# Sheet1.net
KiCad netlist of a schematic drawn in Altium Designer
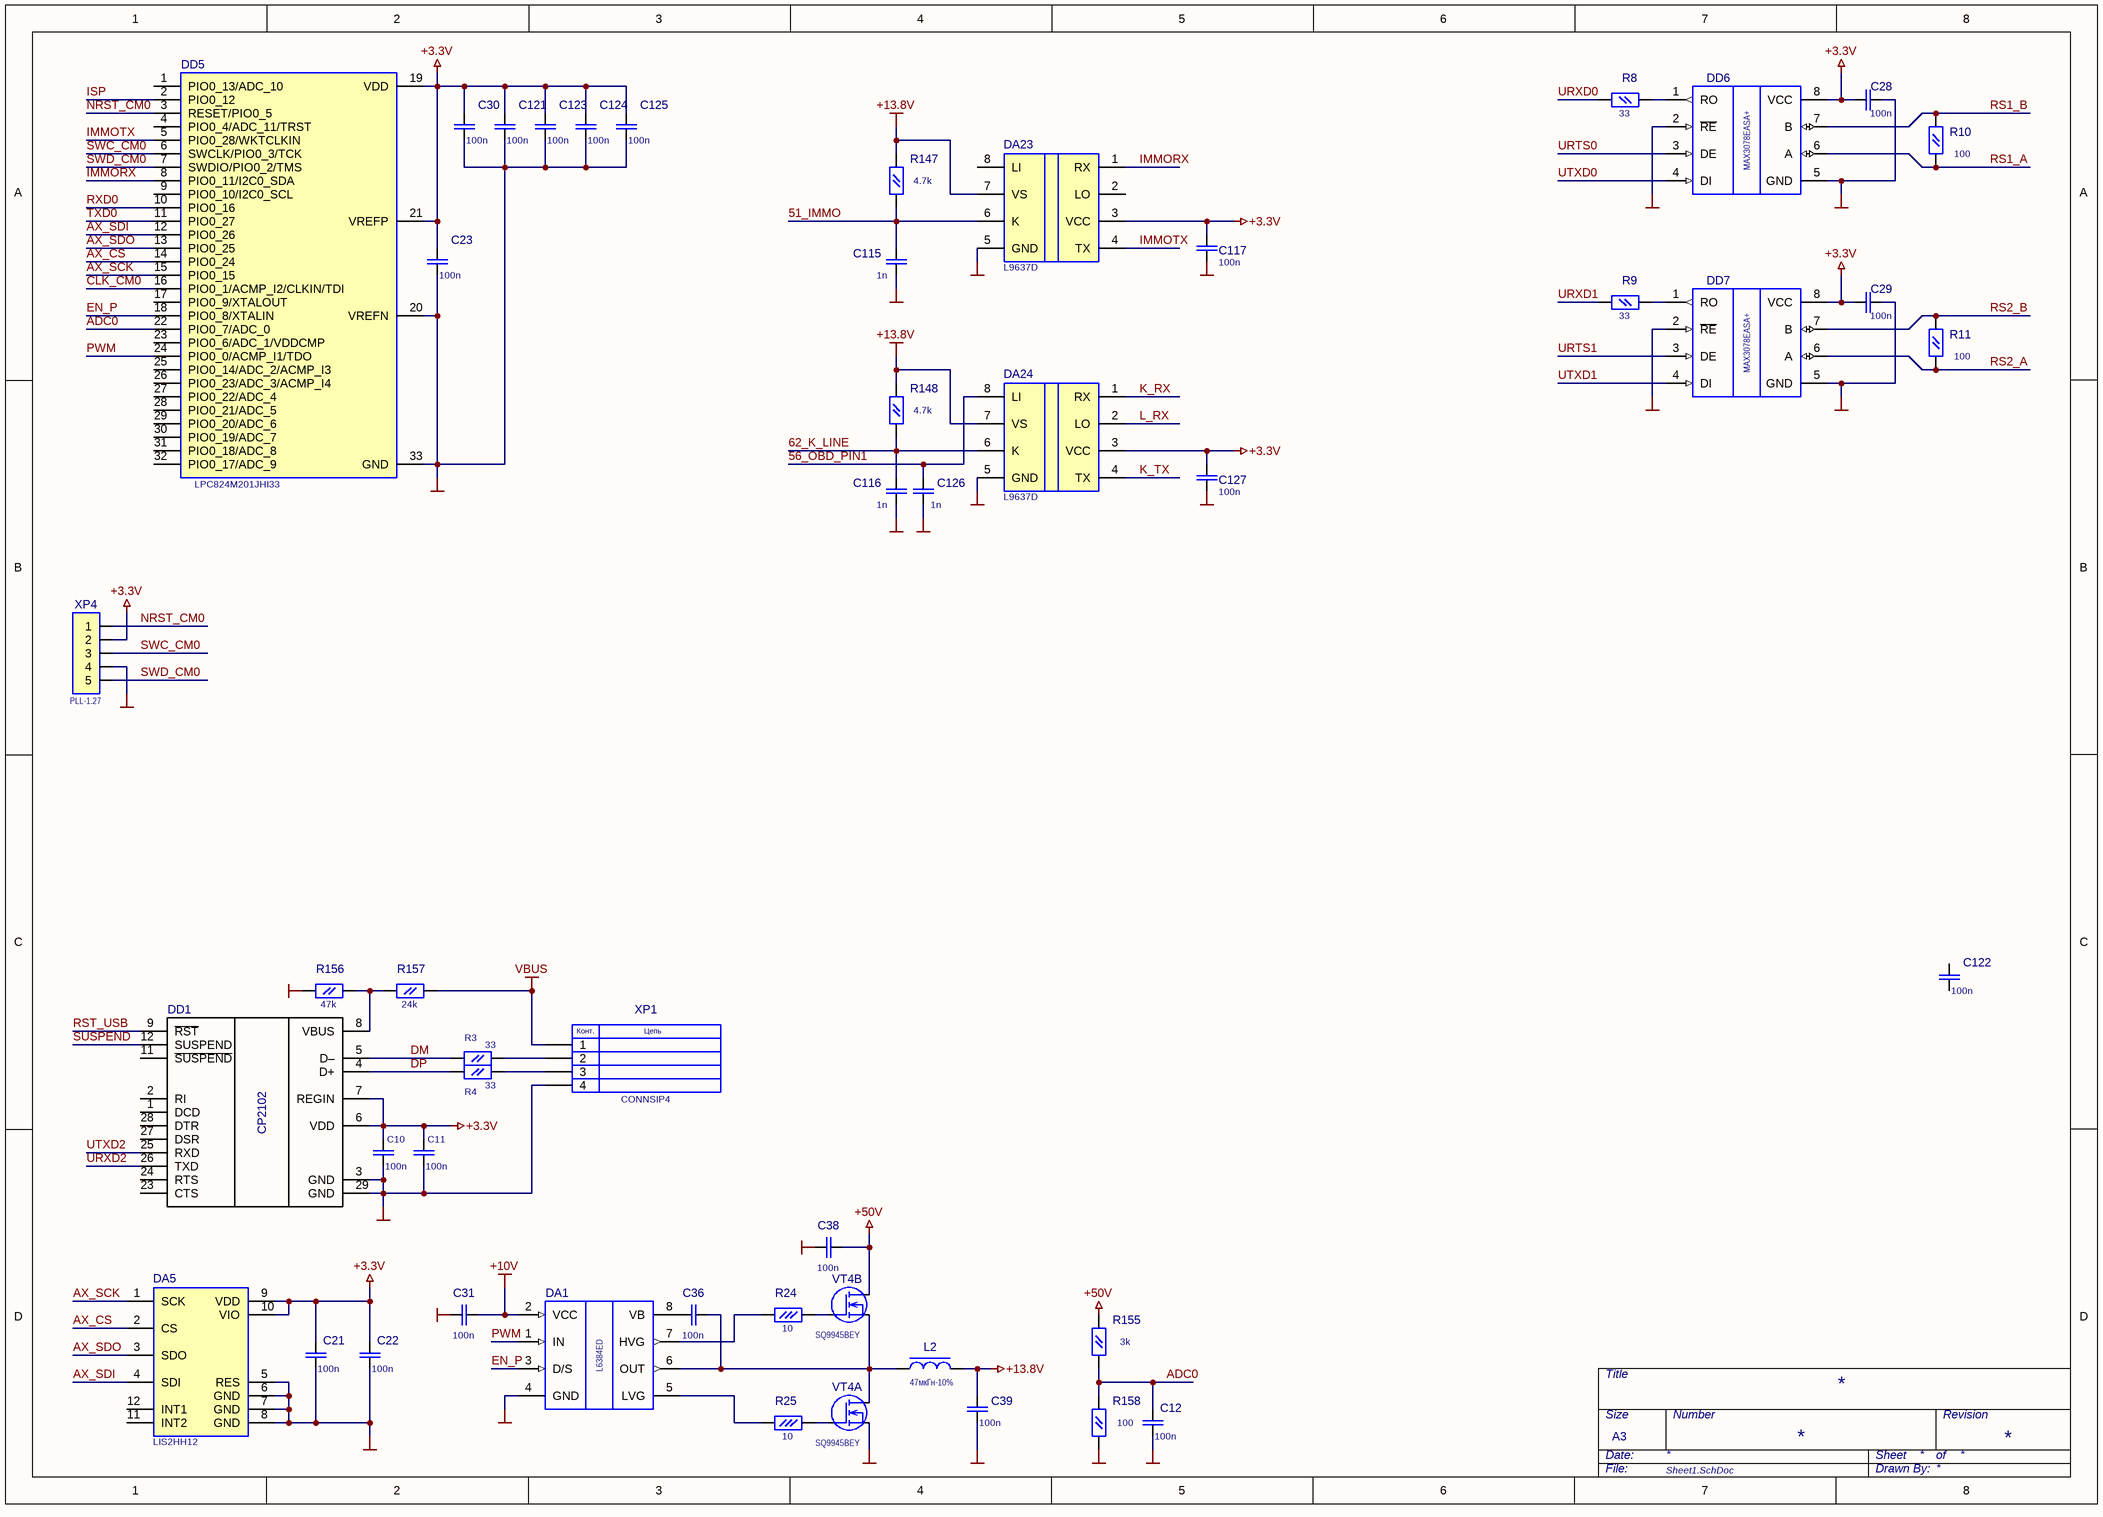
[diagram p0: Sheet1.SchDoc]

(export (version "E")
  (design (tool "Eeschema 10.0.6"))
  (components
    (comp (ref "C10")
      (value "100n")
      (footprint "C0603L")
      (description "C0603")
      (fields (field (name "Comment") "CSMD"))
      (libsource (lib "L1") (part "CSMD"))
    )
    (comp (ref "C11")
      (value "100n")
      (footprint "C0603L")
      (description "C0603")
      (fields (field (name "Comment") "CSMD"))
      (libsource (lib "L1") (part "CSMD"))
    )
    (comp (ref "C12")
      (value "100n")
      (footprint "C0805L")
      (description "C0603")
      (fields (field (name "Comment") "0.1мкФ-25В-X8R-10%"))
      (libsource (lib "L1") (part "CSMD"))
    )
    (comp (ref "C21")
      (value "100n")
      (footprint "C0805L")
      (description "C0603")
      (fields (field (name "Comment") "0.1мкФ-25В-X8R-10%"))
      (libsource (lib "L1") (part "CSMD"))
    )
    (comp (ref "C22")
      (value "100n")
      (footprint "C0805L")
      (description "C0603")
      (fields (field (name "Comment") "0.1мкФ-25В-X8R-10%"))
      (libsource (lib "L1") (part "CSMD"))
    )
    (comp (ref "C23")
      (value "100n")
      (footprint "C0603L")
      (description "C0603")
      (fields (field (name "Comment") "0.1мкФ-25В-X8R-10%"))
      (libsource (lib "L1") (part "CSMD"))
    )
    (comp (ref "C28")
      (value "100n")
      (footprint "C0805")
      (description "C0603")
      (fields (field (name "Comment") "0.1мкФ-50В-X8R-10%"))
      (libsource (lib "L1") (part "CSMD"))
    )
    (comp (ref "C29")
      (value "100n")
      (footprint "C0805")
      (description "C0603")
      (fields (field (name "Comment") "0.1мкФ-50В-X8R-10%"))
      (libsource (lib "L1") (part "CSMD"))
    )
    (comp (ref "C30")
      (value "100n")
      (footprint "C0603L")
      (description "C0603")
      (fields (field (name "Comment") "0.1мкФ-25В-X8R-10%"))
      (libsource (lib "L1") (part "CSMD"))
    )
    (comp (ref "C31")
      (value "100n")
      (footprint "C0805L")
      (description "C0603")
      (fields (field (name "Comment") "CSMD"))
      (libsource (lib "L1") (part "CSMD"))
    )
    (comp (ref "C36")
      (value "100n")
      (footprint "C0805L")
      (description "C0603")
      (fields (field (name "Comment") "CSMD"))
      (libsource (lib "L1") (part "CSMD"))
    )
    (comp (ref "C38")
      (value "100n")
      (footprint "C0805L")
      (description "C0603")
      (fields (field (name "Comment") "CSMD"))
      (libsource (lib "L1") (part "CSMD"))
    )
    (comp (ref "C39")
      (value "100n")
      (footprint "C0805L")
      (description "C0603")
      (fields (field (name "Comment") "0.1мкФ-25В-X8R-10%"))
      (libsource (lib "L1") (part "CSMD"))
    )
    (comp (ref "C115")
      (value "1n")
      (footprint "C0805L")
      (description "C0603")
      (fields (field (name "Comment") "CSMD"))
      (libsource (lib "L1") (part "CSMD"))
    )
    (comp (ref "C116")
      (value "1n")
      (footprint "C0805L")
      (description "C0603")
      (fields (field (name "Comment") "CSMD"))
      (libsource (lib "L1") (part "CSMD"))
    )
    (comp (ref "C117")
      (value "100n")
      (footprint "C0805L")
      (description "C0603")
      (fields (field (name "Comment") "1мкФ-25В-X7R-10%"))
      (libsource (lib "L1") (part "CSMD"))
    )
    (comp (ref "C121")
      (value "100n")
      (footprint "C0603L")
      (description "C0603")
      (fields (field (name "Comment") "0.1мкФ-25В-X8R-10%"))
      (libsource (lib "L1") (part "CSMD"))
    )
    (comp (ref "C122")
      (value "100n")
      (footprint "C0805L")
      (description "C0603")
      (fields (field (name "Comment") "0.1мкФ-50В-X8R-10%"))
      (libsource (lib "L1") (part "CSMD"))
    )
    (comp (ref "C123")
      (value "100n")
      (footprint "C0603L")
      (description "C0603")
      (fields (field (name "Comment") "0.1мкФ-25В-X8R-10%"))
      (libsource (lib "L1") (part "CSMD"))
    )
    (comp (ref "C124")
      (value "100n")
      (footprint "C0603L")
      (description "C0603")
      (fields (field (name "Comment") "0.1мкФ-25В-X8R-10%"))
      (libsource (lib "L1") (part "CSMD"))
    )
    (comp (ref "C125")
      (value "100n")
      (footprint "C0603L")
      (description "C0603")
      (fields (field (name "Comment") "0.1мкФ-25В-X8R-10%"))
      (libsource (lib "L1") (part "CSMD"))
    )
    (comp (ref "C126")
      (value "1n")
      (footprint "C0805L")
      (description "C0603")
      (fields (field (name "Comment") "CSMD"))
      (libsource (lib "L1") (part "CSMD"))
    )
    (comp (ref "C127")
      (value "100n")
      (footprint "C0805L")
      (description "C0603")
      (fields (field (name "Comment") "1мкФ-25В-X7R-10%"))
      (libsource (lib "L1") (part "CSMD"))
    )
    (comp (ref "DA1") (value "L6384ED") (footprint "SOIC8 JEDEC") (libsource (lib "ECULIB") (part "L6384ED")))
    (comp (ref "DA5")
      (value "LIS2HH12")
      (footprint "LGA-12")
      (description "ultra-low-power high-performance 3-axis \"pico\" accelerometer")
      (libsource (lib "L1") (part "LIS2HH12"))
    )
    (comp (ref "DA23")
      (value "L9637D")
      (footprint "SOIC8 JEDEC")
      (description "Monolithic bus driver with ISO 9141 interface")
      (libsource (lib "L1") (part "L9637"))
    )
    (comp (ref "DA24")
      (value "L9637D")
      (footprint "SOIC8 JEDEC")
      (description "Monolithic bus driver with ISO 9141 interface")
      (libsource (lib "L1") (part "L9637"))
    )
    (comp (ref "DD1") (value "CP2102") (footprint "QFN-28") (libsource (lib "L1") (part "CP2102")))
    (comp (ref "DD5")
      (value "LPC824M201JHI33")
      (footprint "HVQFN33")
      (libsource (lib "L1") (part "LPC824M201JHI33"))
    )
    (comp (ref "DD6")
      (value "MAX3078EASA+")
      (footprint "SOIC8 JEDEC")
      (description "MAX3078EASA+ или ISL3179EFBZ или ADM3078EYRZ")
      (libsource (lib "RL1") (part "MAX3088ESA"))
    )
    (comp (ref "DD7")
      (value "MAX3078EASA+")
      (footprint "SOIC8 JEDEC")
      (description "MAX3078EASA+ или ISL3179EFBZ или ADM3078EYRZ")
      (libsource (lib "RL1") (part "MAX3088ESA"))
    )
    (comp (ref "L2") (value "47мкГн-10%") (footprint "L_SDR0604") (libsource (lib "*") (part "DROSSEL3")))
    (comp (ref "R3")
      (value "33")
      (footprint "R0603L")
      (description "R0805")
      (fields (field (name "Comment") "RSMD"))
      (libsource (lib "L1") (part "RSMD"))
    )
    (comp (ref "R4")
      (value "33")
      (footprint "R0603L")
      (description "R0805")
      (fields (field (name "Comment") "RSMD"))
      (libsource (lib "L1") (part "RSMD"))
    )
    (comp (ref "R8")
      (value "33")
      (footprint "R0603L")
      (description "R0805")
      (fields (field (name "Comment") "33-5%"))
      (libsource (lib "L1") (part "RSMD"))
    )
    (comp (ref "R9")
      (value "33")
      (footprint "R0603L")
      (description "R0805")
      (fields (field (name "Comment") "33-5%"))
      (libsource (lib "L1") (part "RSMD"))
    )
    (comp (ref "R10")
      (value "100")
      (footprint "R0805L")
      (description "R0805")
      (fields (field (name "Comment") "100-5%"))
      (libsource (lib "L1") (part "RSMD"))
    )
    (comp (ref "R11")
      (value "100")
      (footprint "R0805L")
      (description "R0805")
      (fields (field (name "Comment") "100-5%"))
      (libsource (lib "L1") (part "RSMD"))
    )
    (comp (ref "R24")
      (value "10")
      (footprint "R0603L")
      (description "R0805")
      (fields (field (name "Comment") "100-5%"))
      (libsource (lib "") (part "RSMD_1"))
    )
    (comp (ref "R25")
      (value "10")
      (footprint "R0603L")
      (description "R0805")
      (fields (field (name "Comment") "100-5%"))
      (libsource (lib "") (part "RSMD_1"))
    )
    (comp (ref "R147")
      (value "4.7k")
      (footprint "R0805L")
      (description "R0805")
      (fields (field (name "Comment") "RSMD"))
      (libsource (lib "L1") (part "RSMD"))
    )
    (comp (ref "R148")
      (value "4.7k")
      (footprint "R0805L")
      (description "R0805")
      (fields (field (name "Comment") "RSMD"))
      (libsource (lib "L1") (part "RSMD"))
    )
    (comp (ref "R155")
      (value "3k")
      (footprint "R0805L")
      (description "R0805")
      (fields (field (name "Comment") "RSMD"))
      (libsource (lib "L1") (part "RSMD"))
    )
    (comp (ref "R156")
      (value "47k")
      (footprint "R0805L")
      (description "R0805")
      (fields (field (name "Comment") "RSMD"))
      (libsource (lib "L1") (part "RSMD"))
    )
    (comp (ref "R157")
      (value "24k")
      (footprint "R0805L")
      (description "R0805")
      (fields (field (name "Comment") "RSMD"))
      (libsource (lib "L1") (part "RSMD"))
    )
    (comp (ref "R158")
      (value "100")
      (footprint "R0805L")
      (description "R0805")
      (fields (field (name "Comment") "RSMD"))
      (libsource (lib "L1") (part "RSMD"))
    )
    (comp (ref "VT4")
      (value "SQ9945BEY")
      (footprint "SOIC8 DBL FET")
      (libsource (lib "L1") (part "SQ9945BEY"))
    )
    (comp (ref "XP1") (value "CONNSIP4") (footprint "SIP4") (libsource (lib "RL1") (part "CONNSIP4")))
    (comp (ref "XP4")
      (value "PLL-1.27")
      (footprint "MHDR1X5")
      (description "Connector")
      (libsource (lib "SCH") (part "CON5"))
    )
  )
  (nets
    (net (code "1") (name "+3.3V") (class "Default")
      (node (ref "C10") (pin "2") (pintype "passive"))
      (node (ref "C11") (pin "2") (pintype "passive"))
      (node (ref "C117") (pin "2") (pintype "passive"))
      (node (ref "C121") (pin "2") (pintype "passive"))
      (node (ref "C123") (pin "2") (pintype "passive"))
      (node (ref "C124") (pin "2") (pintype "passive"))
      (node (ref "C125") (pin "2") (pintype "passive"))
      (node (ref "C127") (pin "2") (pintype "passive"))
      (node (ref "C21") (pin "2") (pintype "passive"))
      (node (ref "C22") (pin "2") (pintype "passive"))
      (node (ref "C23") (pin "2") (pintype "passive"))
      (node (ref "C28") (pin "1") (pintype "passive"))
      (node (ref "C29") (pin "1") (pintype "passive"))
      (node (ref "C30") (pin "2") (pintype "passive"))
      (node (ref "DA23") (pin "3") (pinfunction "VCC_3") (pintype "passive"))
      (node (ref "DA24") (pin "3") (pinfunction "VCC_3") (pintype "passive"))
      (node (ref "DA5") (pin "10") (pinfunction "VIO_10") (pintype "passive"))
      (node (ref "DA5") (pin "9") (pinfunction "VDD_9") (pintype "passive"))
      (node (ref "DD1") (pin "6") (pinfunction "VDD_6") (pintype "passive"))
      (node (ref "DD1") (pin "7") (pinfunction "REGIN_7") (pintype "passive"))
      (node (ref "DD5") (pin "19") (pinfunction "VDD_19") (pintype "passive"))
      (node (ref "DD5") (pin "21") (pinfunction "VREFP_21") (pintype "passive"))
      (node (ref "DD6") (pin "8") (pinfunction "VCC_8") (pintype "power_in"))
      (node (ref "DD7") (pin "8") (pinfunction "VCC_8") (pintype "power_in"))
      (node (ref "XP4") (pin "2") (pinfunction "2_2") (pintype "passive"))
    )
    (net (code "2") (name "+10V") (class "Default")
      (node (ref "C31") (pin "1") (pintype "passive"))
      (node (ref "DA1") (pin "2") (pinfunction "VCC_2") (pintype "input"))
    )
    (net (code "3") (name "+13.8V") (class "Default")
      (node (ref "C39") (pin "1") (pintype "passive"))
      (node (ref "DA23") (pin "7") (pinfunction "VS_7") (pintype "passive"))
      (node (ref "DA24") (pin "7") (pinfunction "VS_7") (pintype "passive"))
      (node (ref "L2") (pin "1") (pinfunction "1_1") (pintype "passive"))
      (node (ref "R147") (pin "2") (pinfunction "Pin2_2") (pintype "passive"))
      (node (ref "R148") (pin "2") (pinfunction "Pin2_2") (pintype "passive"))
    )
    (net (code "4") (name "+50V") (class "Default")
      (node (ref "C38") (pin "1") (pintype "passive"))
      (node (ref "R155") (pin "2") (pinfunction "Pin2_2") (pintype "passive"))
      (node (ref "VT4") (pin "5") (pintype "passive"))
    )
    (net (code "5") (name "/51_IMMO") (class "Default")
      (node (ref "C115") (pin "1") (pintype "passive"))
      (node (ref "DA23") (pin "6") (pinfunction "K_6") (pintype "passive"))
      (node (ref "R147") (pin "1") (pinfunction "Pin1_1") (pintype "passive"))
    )
    (net (code "6") (name "/56_OBD_PIN1") (class "Default")
      (node (ref "C126") (pin "1") (pintype "passive"))
      (node (ref "DA24") (pin "8") (pinfunction "LI_8") (pintype "passive"))
    )
    (net (code "7") (name "/62_K_LINE") (class "Default")
      (node (ref "C116") (pin "1") (pintype "passive"))
      (node (ref "DA24") (pin "6") (pinfunction "K_6") (pintype "passive"))
      (node (ref "R148") (pin "1") (pinfunction "Pin1_1") (pintype "passive"))
    )
    (net (code "8") (name "/ADC0") (class "Default")
      (node (ref "C12") (pin "2") (pintype "passive"))
      (node (ref "DD5") (pin "22") (pinfunction "PIO0_7/ADC_0_22") (pintype "passive"))
      (node (ref "R155") (pin "1") (pinfunction "Pin1_1") (pintype "passive"))
      (node (ref "R158") (pin "2") (pinfunction "Pin2_2") (pintype "passive"))
    )
    (net (code "9") (name "/AX_CS") (class "Default")
      (node (ref "DA5") (pin "2") (pinfunction "CS_2") (pintype "passive"))
      (node (ref "DD5") (pin "14") (pinfunction "PIO0_24_14") (pintype "passive"))
    )
    (net (code "10") (name "/AX_SCK") (class "Default")
      (node (ref "DA5") (pin "1") (pinfunction "SCK_1") (pintype "passive"))
      (node (ref "DD5") (pin "15") (pinfunction "PIO0_15_15") (pintype "passive"))
    )
    (net (code "11") (name "/AX_SDI") (class "Default")
      (node (ref "DA5") (pin "4") (pinfunction "SDI_4") (pintype "passive"))
      (node (ref "DD5") (pin "12") (pinfunction "PIO0_26_12") (pintype "passive"))
    )
    (net (code "12") (name "/AX_SDO") (class "Default")
      (node (ref "DA5") (pin "3") (pinfunction "SDO_3") (pintype "passive"))
      (node (ref "DD5") (pin "13") (pinfunction "PIO0_25_13") (pintype "passive"))
    )
    (net (code "13") (name "/CLK_CM0") (class "Default")
      (node (ref "DD5") (pin "16") (pinfunction "PIO0_1/ACMP_I2/CLKIN/TDI_16") (pintype "passive"))
    )
    (net (code "14") (name "/DM") (class "Default")
      (node (ref "DD1") (pin "5") (pinfunction "D_5") (pintype "passive"))
      (node (ref "R3") (pin "1") (pinfunction "Pin1_1") (pintype "passive"))
    )
    (net (code "15") (name "/DP") (class "Default")
      (node (ref "DD1") (pin "4") (pinfunction "D+_4") (pintype "passive"))
      (node (ref "R4") (pin "1") (pinfunction "Pin1_1") (pintype "passive"))
    )
    (net (code "16") (name "/EN_P") (class "Default")
      (node (ref "DA1") (pin "3") (pinfunction "D/S_3") (pintype "input"))
      (node (ref "DD5") (pin "18") (pinfunction "PIO0_8/XTALIN_18") (pintype "passive"))
    )
    (net (code "17") (name "/IMMORX") (class "Default")
      (node (ref "DA23") (pin "1") (pinfunction "RX_1") (pintype "passive"))
      (node (ref "DD5") (pin "8") (pinfunction "PIO0_11/I2C0_SDA_8") (pintype "passive"))
    )
    (net (code "18") (name "/IMMOTX") (class "Default")
      (node (ref "DA23") (pin "4") (pinfunction "TX_4") (pintype "passive"))
      (node (ref "DD5") (pin "5") (pinfunction "PIO0_28/WKTCLKIN_5") (pintype "passive"))
    )
    (net (code "19") (name "/ISP") (class "Default")
      (node (ref "DD5") (pin "2") (pinfunction "PIO0_12_2") (pintype "passive"))
    )
    (net (code "20") (name "/K_RX") (class "Default")
      (node (ref "DA24") (pin "1") (pinfunction "RX_1") (pintype "passive"))
    )
    (net (code "21") (name "/K_TX") (class "Default")
      (node (ref "DA24") (pin "4") (pinfunction "TX_4") (pintype "passive"))
    )
    (net (code "22") (name "/L_RX") (class "Default")
      (node (ref "DA24") (pin "2") (pinfunction "LO_2") (pintype "passive"))
    )
    (net (code "23") (name "/NRST_CM0") (class "Default")
      (node (ref "DD5") (pin "3") (pinfunction "RESET/PIO0_5_3") (pintype "passive"))
      (node (ref "XP4") (pin "1") (pinfunction "1_1") (pintype "passive"))
    )
    (net (code "24") (name "/PWM") (class "Default")
      (node (ref "DA1") (pin "1") (pinfunction "IN_1") (pintype "input"))
      (node (ref "DD5") (pin "24") (pinfunction "PIO0_0/ACMP_I1/TDO_24") (pintype "passive"))
    )
    (net (code "25") (name "/RS1_A") (class "Default")
      (node (ref "DD6") (pin "6") (pinfunction "A_6") (pintype "bidirectional"))
      (node (ref "R10") (pin "1") (pinfunction "Pin1_1") (pintype "passive"))
    )
    (net (code "26") (name "/RS1_B") (class "Default")
      (node (ref "DD6") (pin "7") (pinfunction "B_7") (pintype "bidirectional"))
      (node (ref "R10") (pin "2") (pinfunction "Pin2_2") (pintype "passive"))
    )
    (net (code "27") (name "/RS2_A") (class "Default")
      (node (ref "DD7") (pin "6") (pinfunction "A_6") (pintype "bidirectional"))
      (node (ref "R11") (pin "1") (pinfunction "Pin1_1") (pintype "passive"))
    )
    (net (code "28") (name "/RS2_B") (class "Default")
      (node (ref "DD7") (pin "7") (pinfunction "B_7") (pintype "bidirectional"))
      (node (ref "R11") (pin "2") (pinfunction "Pin2_2") (pintype "passive"))
    )
    (net (code "29") (name "/RST_USB") (class "Default")
      (node (ref "DD1") (pin "9") (pinfunction "~{RST}_9") (pintype "passive"))
    )
    (net (code "30") (name "/RXD0") (class "Default")
      (node (ref "DD5") (pin "10") (pinfunction "PIO0_16_10") (pintype "passive"))
    )
    (net (code "31") (name "/SUSPEND") (class "Default")
      (node (ref "DD1") (pin "12") (pinfunction "SUSPEND_12") (pintype "passive"))
    )
    (net (code "32") (name "/SWC_CM0") (class "Default")
      (node (ref "DD5") (pin "6") (pinfunction "SWCLK/PIO0_3/TCK_6") (pintype "passive"))
      (node (ref "XP4") (pin "3") (pinfunction "3_3") (pintype "passive"))
    )
    (net (code "33") (name "/SWD_CM0") (class "Default")
      (node (ref "DD5") (pin "7") (pinfunction "SWDIO/PIO0_2/TMS_7") (pintype "passive"))
      (node (ref "XP4") (pin "5") (pinfunction "5_5") (pintype "passive"))
    )
    (net (code "34") (name "/TXD0") (class "Default")
      (node (ref "DD5") (pin "11") (pinfunction "PIO0_27_11") (pintype "passive"))
    )
    (net (code "35") (name "/URTS0") (class "Default")
      (node (ref "DD6") (pin "3") (pinfunction "DE_3") (pintype "input"))
    )
    (net (code "36") (name "/URTS1") (class "Default")
      (node (ref "DD7") (pin "3") (pinfunction "DE_3") (pintype "input"))
    )
    (net (code "37") (name "/URXD0") (class "Default")
      (node (ref "R8") (pin "2") (pinfunction "Pin2_2") (pintype "passive"))
    )
    (net (code "38") (name "/URXD1") (class "Default")
      (node (ref "R9") (pin "2") (pinfunction "Pin2_2") (pintype "passive"))
    )
    (net (code "39") (name "/URXD2") (class "Default")
      (node (ref "DD1") (pin "26") (pinfunction "TXD_26") (pintype "passive"))
    )
    (net (code "40") (name "/UTXD0") (class "Default")
      (node (ref "DD6") (pin "4") (pinfunction "DI_4") (pintype "input"))
    )
    (net (code "41") (name "/UTXD1") (class "Default")
      (node (ref "DD7") (pin "4") (pinfunction "DI_4") (pintype "input"))
    )
    (net (code "42") (name "/UTXD2") (class "Default")
      (node (ref "DD1") (pin "25") (pinfunction "RXD_25") (pintype "passive"))
    )
    (net (code "43") (name "GND") (class "Default")
      (node (ref "C10") (pin "1") (pintype "passive"))
      (node (ref "C11") (pin "1") (pintype "passive"))
      (node (ref "C115") (pin "2") (pintype "passive"))
      (node (ref "C116") (pin "2") (pintype "passive"))
      (node (ref "C117") (pin "1") (pintype "passive"))
      (node (ref "C12") (pin "1") (pintype "passive"))
      (node (ref "C121") (pin "1") (pintype "passive"))
      (node (ref "C123") (pin "1") (pintype "passive"))
      (node (ref "C124") (pin "1") (pintype "passive"))
      (node (ref "C125") (pin "1") (pintype "passive"))
      (node (ref "C126") (pin "2") (pintype "passive"))
      (node (ref "C127") (pin "1") (pintype "passive"))
      (node (ref "C21") (pin "1") (pintype "passive"))
      (node (ref "C22") (pin "1") (pintype "passive"))
      (node (ref "C23") (pin "1") (pintype "passive"))
      (node (ref "C28") (pin "2") (pintype "passive"))
      (node (ref "C29") (pin "2") (pintype "passive"))
      (node (ref "C30") (pin "1") (pintype "passive"))
      (node (ref "C31") (pin "2") (pintype "passive"))
      (node (ref "C38") (pin "2") (pintype "passive"))
      (node (ref "C39") (pin "2") (pintype "passive"))
      (node (ref "DA1") (pin "4") (pinfunction "GND_4") (pintype "power_in"))
      (node (ref "DA23") (pin "5") (pinfunction "GND_5") (pintype "passive"))
      (node (ref "DA24") (pin "5") (pinfunction "GND_5") (pintype "passive"))
      (node (ref "DA5") (pin "5") (pinfunction "RES_5") (pintype "passive"))
      (node (ref "DA5") (pin "6") (pinfunction "GND_6") (pintype "passive"))
      (node (ref "DA5") (pin "7") (pinfunction "GND_7") (pintype "passive"))
      (node (ref "DA5") (pin "8") (pinfunction "GND_8") (pintype "passive"))
      (node (ref "DD1") (pin "29") (pinfunction "GND_29") (pintype "passive"))
      (node (ref "DD1") (pin "3") (pinfunction "GND_3") (pintype "passive"))
      (node (ref "DD5") (pin "20") (pinfunction "VREFN_20") (pintype "passive"))
      (node (ref "DD5") (pin "33") (pinfunction "GND_33") (pintype "passive"))
      (node (ref "DD6") (pin "2") (pinfunction "~{RE}_2") (pintype "input"))
      (node (ref "DD6") (pin "5") (pinfunction "GND_5") (pintype "power_in"))
      (node (ref "DD7") (pin "2") (pinfunction "~{RE}_2") (pintype "input"))
      (node (ref "DD7") (pin "5") (pinfunction "GND_5") (pintype "power_in"))
      (node (ref "R156") (pin "1") (pinfunction "Pin1_1") (pintype "passive"))
      (node (ref "R158") (pin "1") (pinfunction "Pin1_1") (pintype "passive"))
      (node (ref "VT4") (pin "1") (pintype "passive"))
      (node (ref "XP1") (pin "4") (pinfunction "4_4") (pintype "passive"))
      (node (ref "XP4") (pin "4") (pinfunction "4_4") (pintype "passive"))
    )
    (net (code "44") (name "Net-(DA1-HVG)") (class "Default")
      (node (ref "DA1") (pin "7") (pinfunction "HVG_7") (pintype "output"))
      (node (ref "R24") (pin "2") (pintype "passive"))
    )
    (net (code "45") (name "Net-(DA1-LVG)") (class "Default")
      (node (ref "DA1") (pin "5") (pinfunction "LVG_5") (pintype "power_in"))
      (node (ref "R25") (pin "2") (pintype "passive"))
    )
    (net (code "46") (name "Net-(DA1-OUT)") (class "Default")
      (node (ref "C36") (pin "1") (pintype "passive"))
      (node (ref "DA1") (pin "6") (pinfunction "OUT_6") (pintype "output"))
      (node (ref "L2") (pin "2") (pinfunction "2_2") (pintype "passive"))
      (node (ref "VT4") (pin "3") (pintype "passive"))
      (node (ref "VT4") (pin "6") (pintype "passive"))
    )
    (net (code "47") (name "Net-(DA1-VB)") (class "Default")
      (node (ref "C36") (pin "2") (pintype "passive"))
      (node (ref "DA1") (pin "8") (pinfunction "VB_8") (pintype "power_in"))
    )
    (net (code "48") (name "Net-(DD1-VBUS)") (class "Default")
      (node (ref "DD1") (pin "8") (pinfunction "VBUS_8") (pintype "passive"))
      (node (ref "R156") (pin "2") (pinfunction "Pin2_2") (pintype "passive"))
      (node (ref "R157") (pin "1") (pinfunction "Pin1_1") (pintype "passive"))
    )
    (net (code "49") (name "Net-(DD6-RO)") (class "Default")
      (node (ref "DD6") (pin "1") (pinfunction "RO_1") (pintype "output"))
      (node (ref "R8") (pin "1") (pinfunction "Pin1_1") (pintype "passive"))
    )
    (net (code "50") (name "Net-(DD7-RO)") (class "Default")
      (node (ref "DD7") (pin "1") (pinfunction "RO_1") (pintype "output"))
      (node (ref "R9") (pin "1") (pinfunction "Pin1_1") (pintype "passive"))
    )
    (net (code "51") (name "Net-(R3-Pin2)") (class "Default")
      (node (ref "R3") (pin "2") (pinfunction "Pin2_2") (pintype "passive"))
      (node (ref "XP1") (pin "2") (pinfunction "2_2") (pintype "passive"))
    )
    (net (code "52") (name "Net-(R4-Pin2)") (class "Default")
      (node (ref "R4") (pin "2") (pinfunction "Pin2_2") (pintype "passive"))
      (node (ref "XP1") (pin "3") (pinfunction "3_3") (pintype "passive"))
    )
    (net (code "53") (name "Net-(R24-Pad1)") (class "Default")
      (node (ref "R24") (pin "1") (pintype "passive"))
      (node (ref "VT4") (pin "4") (pintype "passive"))
    )
    (net (code "54") (name "Net-(R25-Pad1)") (class "Default")
      (node (ref "R25") (pin "1") (pintype "passive"))
      (node (ref "VT4") (pin "2") (pintype "passive"))
    )
    (net (code "55") (name "VBUS") (class "Default")
      (node (ref "R157") (pin "2") (pinfunction "Pin2_2") (pintype "passive"))
      (node (ref "XP1") (pin "1") (pinfunction "1_1") (pintype "passive"))
    )
    (net (code "56") (name "unconnected-(C122-Pad1)") (class "Default")
      (node (ref "C122") (pin "1") (pintype "passive"))
    )
    (net (code "57") (name "unconnected-(C122-Pad2)") (class "Default")
      (node (ref "C122") (pin "2") (pintype "passive"))
    )
    (net (code "58") (name "unconnected-(DA5-INT1-Pad12)") (class "Default")
      (node (ref "DA5") (pin "12") (pinfunction "INT1_12") (pintype "passive"))
    )
    (net (code "59") (name "unconnected-(DA5-INT2-Pad11)") (class "Default")
      (node (ref "DA5") (pin "11") (pinfunction "INT2_11") (pintype "passive"))
    )
    (net (code "60") (name "unconnected-(DA23-LI-Pad8)") (class "Default")
      (node (ref "DA23") (pin "8") (pinfunction "LI_8") (pintype "passive"))
    )
    (net (code "61") (name "unconnected-(DA23-LO-Pad2)") (class "Default")
      (node (ref "DA23") (pin "2") (pinfunction "LO_2") (pintype "passive"))
    )
    (net (code "62") (name "unconnected-(DD1-CTS-Pad23)") (class "Default")
      (node (ref "DD1") (pin "23") (pinfunction "CTS_23") (pintype "passive"))
    )
    (net (code "63") (name "unconnected-(DD1-DCD-Pad1)") (class "Default")
      (node (ref "DD1") (pin "1") (pinfunction "DCD_1") (pintype "passive"))
    )
    (net (code "64") (name "unconnected-(DD1-DSR-Pad27)") (class "Default")
      (node (ref "DD1") (pin "27") (pinfunction "DSR_27") (pintype "passive"))
    )
    (net (code "65") (name "unconnected-(DD1-DTR-Pad28)") (class "Default")
      (node (ref "DD1") (pin "28") (pinfunction "DTR_28") (pintype "passive"))
    )
    (net (code "66") (name "unconnected-(DD1-NC-Pad10)") (class "Default")
      (node (ref "DD1") (pin "10") (pinfunction "NC_10") (pintype "passive"))
    )
    (net (code "67") (name "unconnected-(DD1-NC-Pad13)") (class "Default")
      (node (ref "DD1") (pin "13") (pinfunction "NC_13") (pintype "passive"))
    )
    (net (code "68") (name "unconnected-(DD1-NC-Pad14)") (class "Default")
      (node (ref "DD1") (pin "14") (pinfunction "NC_14") (pintype "passive"))
    )
    (net (code "69") (name "unconnected-(DD1-NC-Pad15)") (class "Default")
      (node (ref "DD1") (pin "15") (pinfunction "NC_15") (pintype "passive"))
    )
    (net (code "70") (name "unconnected-(DD1-NC-Pad16)") (class "Default")
      (node (ref "DD1") (pin "16") (pinfunction "NC_16") (pintype "passive"))
    )
    (net (code "71") (name "unconnected-(DD1-NC-Pad17)") (class "Default")
      (node (ref "DD1") (pin "17") (pinfunction "NC_17") (pintype "passive"))
    )
    (net (code "72") (name "unconnected-(DD1-NC-Pad18)") (class "Default")
      (node (ref "DD1") (pin "18") (pinfunction "NC_18") (pintype "passive"))
    )
    (net (code "73") (name "unconnected-(DD1-NC-Pad19)") (class "Default")
      (node (ref "DD1") (pin "19") (pinfunction "NC_19") (pintype "passive"))
    )
    (net (code "74") (name "unconnected-(DD1-NC-Pad20)") (class "Default")
      (node (ref "DD1") (pin "20") (pinfunction "NC_20") (pintype "passive"))
    )
    (net (code "75") (name "unconnected-(DD1-NC-Pad21)") (class "Default")
      (node (ref "DD1") (pin "21") (pinfunction "NC_21") (pintype "passive"))
    )
    (net (code "76") (name "unconnected-(DD1-NC-Pad22)") (class "Default")
      (node (ref "DD1") (pin "22") (pinfunction "NC_22") (pintype "passive"))
    )
    (net (code "77") (name "unconnected-(DD1-RI-Pad2)") (class "Default")
      (node (ref "DD1") (pin "2") (pinfunction "RI_2") (pintype "passive"))
    )
    (net (code "78") (name "unconnected-(DD1-RTS-Pad24)") (class "Default")
      (node (ref "DD1") (pin "24") (pinfunction "RTS_24") (pintype "passive"))
    )
    (net (code "79") (name "unconnected-(DD1-~{SUSPEND}-Pad11)") (class "Default")
      (node (ref "DD1") (pin "11") (pinfunction "~{SUSPEND}_11") (pintype "passive"))
    )
    (net (code "80") (name "unconnected-(DD5-PIO0_4{slash}ADC_11{slash}TRST-Pad4)") (class "Default")
      (node (ref "DD5") (pin "4") (pinfunction "PIO0_4/ADC_11/TRST_4") (pintype "passive"))
    )
    (net (code "81") (name "unconnected-(DD5-PIO0_6{slash}ADC_1{slash}VDDCMP-Pad23)") (class "Default")
      (node (ref "DD5") (pin "23") (pinfunction "PIO0_6/ADC_1/VDDCMP_23") (pintype "passive"))
    )
    (net (code "82") (name "unconnected-(DD5-PIO0_9{slash}XTALOUT-Pad17)") (class "Default")
      (node (ref "DD5") (pin "17") (pinfunction "PIO0_9/XTALOUT_17") (pintype "passive"))
    )
    (net (code "83") (name "unconnected-(DD5-PIO0_10{slash}I2C0_SCL-Pad9)") (class "Default")
      (node (ref "DD5") (pin "9") (pinfunction "PIO0_10/I2C0_SCL_9") (pintype "passive"))
    )
    (net (code "84") (name "unconnected-(DD5-PIO0_13{slash}ADC_10-Pad1)") (class "Default")
      (node (ref "DD5") (pin "1") (pinfunction "PIO0_13/ADC_10_1") (pintype "passive"))
    )
    (net (code "85") (name "unconnected-(DD5-PIO0_14{slash}ADC_2{slash}ACMP_I3-Pad25)") (class "Default")
      (node (ref "DD5") (pin "25") (pinfunction "PIO0_14/ADC_2/ACMP_I3_25") (pintype "passive"))
    )
    (net (code "86") (name "unconnected-(DD5-PIO0_17{slash}ADC_9-Pad32)") (class "Default")
      (node (ref "DD5") (pin "32") (pinfunction "PIO0_17/ADC_9_32") (pintype "passive"))
    )
    (net (code "87") (name "unconnected-(DD5-PIO0_18{slash}ADC_8-Pad31)") (class "Default")
      (node (ref "DD5") (pin "31") (pinfunction "PIO0_18/ADC_8_31") (pintype "passive"))
    )
    (net (code "88") (name "unconnected-(DD5-PIO0_19{slash}ADC_7-Pad30)") (class "Default")
      (node (ref "DD5") (pin "30") (pinfunction "PIO0_19/ADC_7_30") (pintype "passive"))
    )
    (net (code "89") (name "unconnected-(DD5-PIO0_20{slash}ADC_6-Pad29)") (class "Default")
      (node (ref "DD5") (pin "29") (pinfunction "PIO0_20/ADC_6_29") (pintype "passive"))
    )
    (net (code "90") (name "unconnected-(DD5-PIO0_21{slash}ADC_5-Pad28)") (class "Default")
      (node (ref "DD5") (pin "28") (pinfunction "PIO0_21/ADC_5_28") (pintype "passive"))
    )
    (net (code "91") (name "unconnected-(DD5-PIO0_22{slash}ADC_4-Pad27)") (class "Default")
      (node (ref "DD5") (pin "27") (pinfunction "PIO0_22/ADC_4_27") (pintype "passive"))
    )
    (net (code "92") (name "unconnected-(DD5-PIO0_23{slash}ADC_3{slash}ACMP_I4-Pad26)") (class "Default")
      (node (ref "DD5") (pin "26") (pinfunction "PIO0_23/ADC_3/ACMP_I4_26") (pintype "passive"))
    )
  )
)
